# open-usb-can.net
KiCad netlist of a schematic drawn in EAGLE
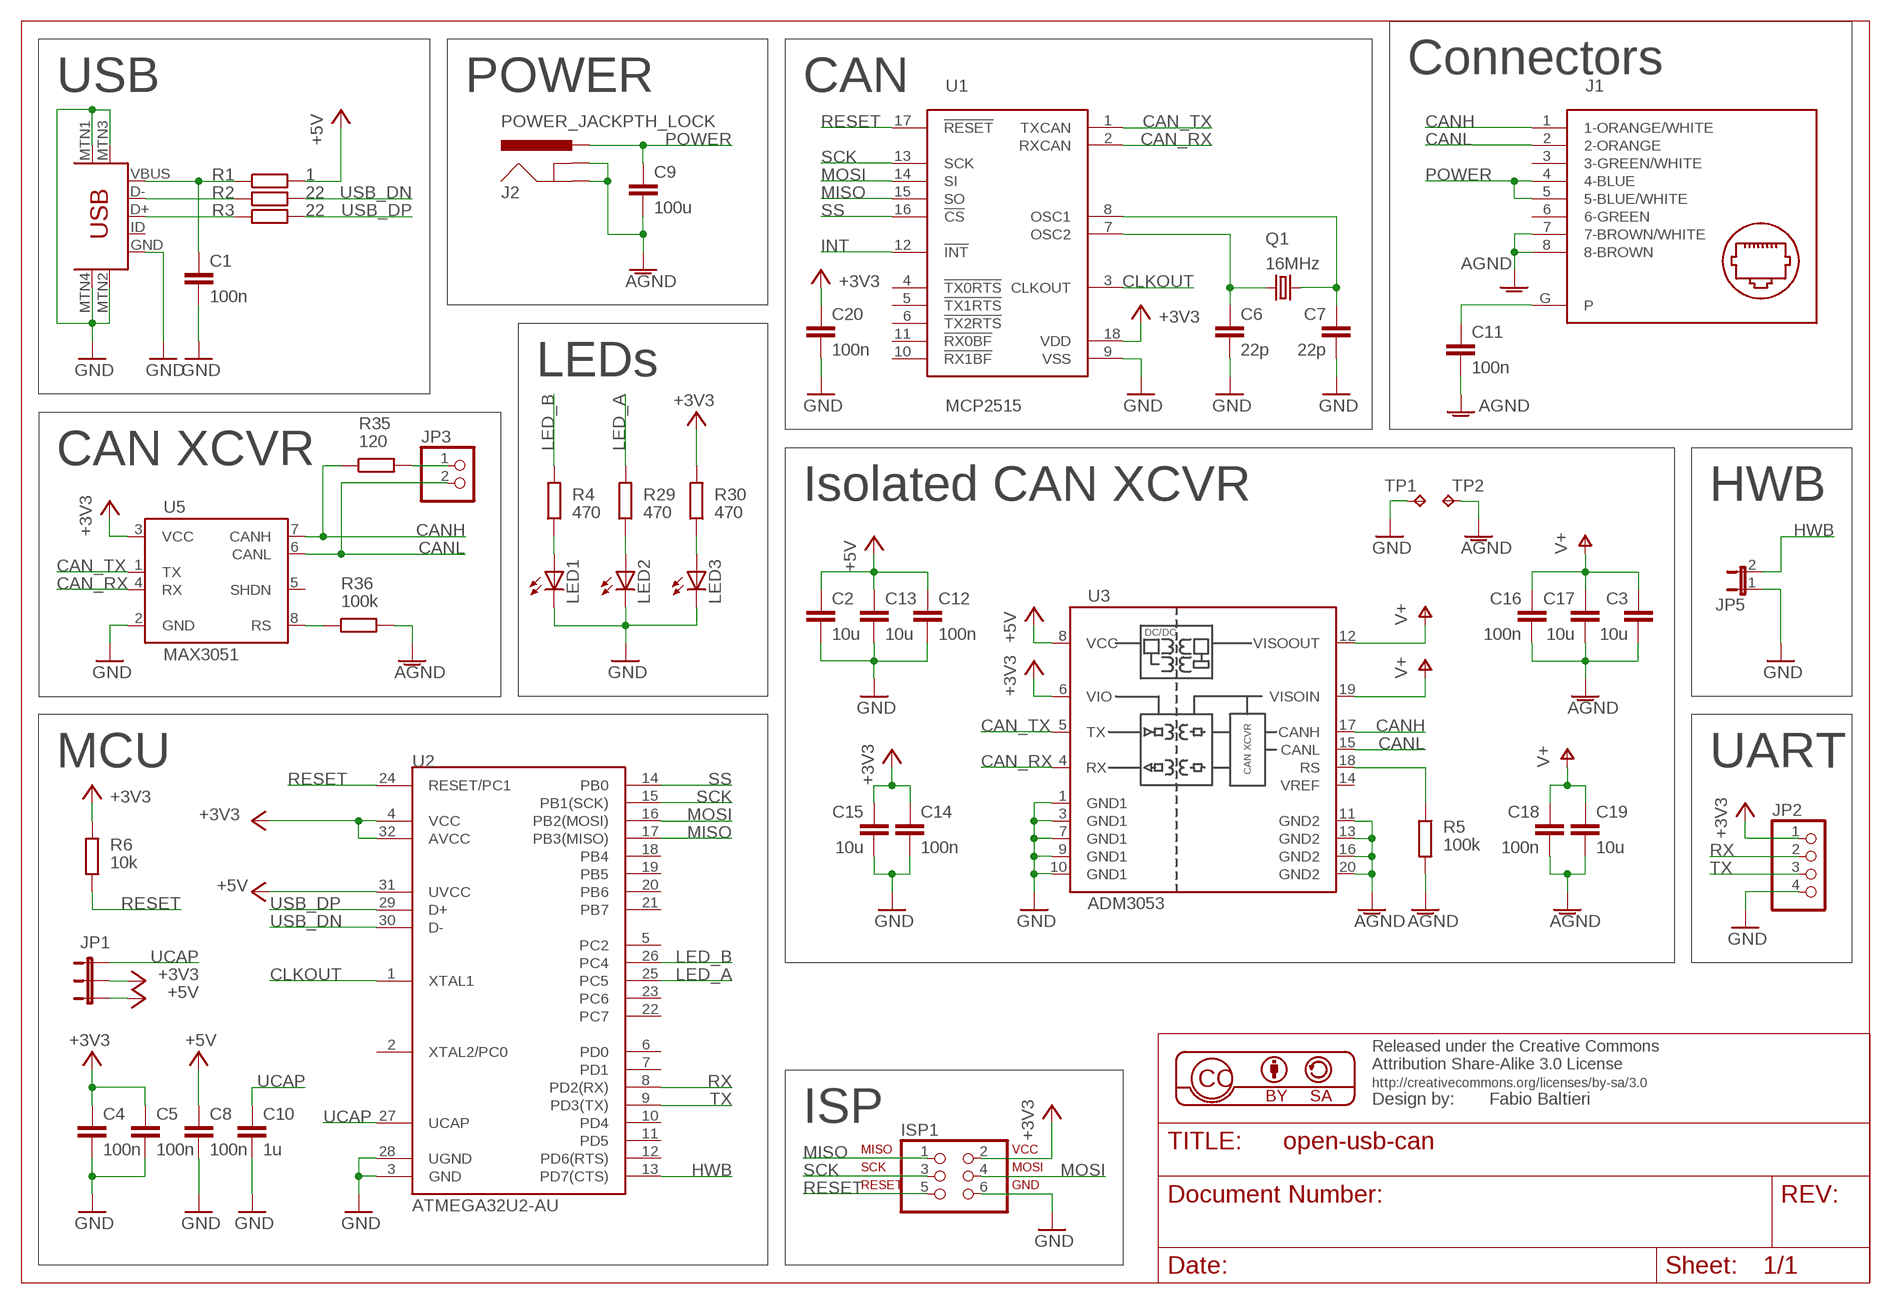
[diagram p0: schematic, sheet 1]

(export (version "E")
  (design (tool "Eeschema 10.0.6"))
  (components
    (comp (ref "C1")
      (value "100n")
      (footprint "eagle-import:C0805")
      (libsource (lib "eagle-import") (part "C-EUC0805"))
    )
    (comp (ref "C2")
      (value "10u")
      (footprint "eagle-import:C0805")
      (libsource (lib "eagle-import") (part "C-EUC0805"))
    )
    (comp (ref "C3")
      (value "10u")
      (footprint "eagle-import:C0805")
      (libsource (lib "eagle-import") (part "C-EUC0805"))
    )
    (comp (ref "C4")
      (value "100n")
      (footprint "eagle-import:C0805")
      (libsource (lib "eagle-import") (part "C-EUC0805"))
    )
    (comp (ref "C5")
      (value "100n")
      (footprint "eagle-import:C0805")
      (libsource (lib "eagle-import") (part "C-EUC0805"))
    )
    (comp (ref "C6")
      (value "22p")
      (footprint "eagle-import:C0805")
      (libsource (lib "eagle-import") (part "C-EUC0805"))
    )
    (comp (ref "C7")
      (value "22p")
      (footprint "eagle-import:C0805")
      (libsource (lib "eagle-import") (part "C-EUC0805"))
    )
    (comp (ref "C8")
      (value "100n")
      (footprint "eagle-import:C0805")
      (libsource (lib "eagle-import") (part "C-EUC0805"))
    )
    (comp (ref "C9")
      (value "100u")
      (footprint "eagle-import:C0805")
      (libsource (lib "eagle-import") (part "C-EUC0805"))
    )
    (comp (ref "C10")
      (value "1u")
      (footprint "eagle-import:C0805")
      (libsource (lib "eagle-import") (part "C-EUC0805"))
    )
    (comp (ref "C11")
      (value "100n")
      (footprint "eagle-import:C0805")
      (libsource (lib "eagle-import") (part "C-EUC0805"))
    )
    (comp (ref "C12")
      (value "100n")
      (footprint "eagle-import:C0805")
      (libsource (lib "eagle-import") (part "C-EUC0805"))
    )
    (comp (ref "C13")
      (value "10u")
      (footprint "eagle-import:C0805")
      (libsource (lib "eagle-import") (part "C-EUC0805"))
    )
    (comp (ref "C14")
      (value "100n")
      (footprint "eagle-import:C0805")
      (libsource (lib "eagle-import") (part "C-EUC0805"))
    )
    (comp (ref "C15")
      (value "10u")
      (footprint "eagle-import:C0805")
      (libsource (lib "eagle-import") (part "C-EUC0805"))
    )
    (comp (ref "C16")
      (value "100n")
      (footprint "eagle-import:C0805")
      (libsource (lib "eagle-import") (part "C-EUC0805"))
    )
    (comp (ref "C17")
      (value "10u")
      (footprint "eagle-import:C0805")
      (libsource (lib "eagle-import") (part "C-EUC0805"))
    )
    (comp (ref "C18")
      (value "100n")
      (footprint "eagle-import:C0805")
      (libsource (lib "eagle-import") (part "C-EUC0805"))
    )
    (comp (ref "C19")
      (value "10u")
      (footprint "eagle-import:C0805")
      (libsource (lib "eagle-import") (part "C-EUC0805"))
    )
    (comp (ref "C20")
      (value "100n")
      (footprint "eagle-import:C0805")
      (libsource (lib "eagle-import") (part "C-EUC0805"))
    )
    (comp (ref "ISP1")
      (value "ISP-AVR910PTH")
      (footprint "eagle-import:2X03")
      (libsource (lib "eagle-import") (part "ISP-AVR910PTH"))
    )
    (comp (ref "J1")
      (value "NE8FAH")
      (footprint "eagle-import:NE8FAH")
      (libsource (lib "eagle-import") (part "NE8FAH"))
    )
    (comp (ref "J2")
      (value "POWER_JACKPTH_LOCK")
      (footprint "eagle-import:POWER_JACK_PTH_LOCK")
      (libsource (lib "eagle-import") (part "POWER_JACKPTH_LOCK"))
    )
    (comp (ref "JP1")
      (value "JUMPER-3SMD")
      (footprint "eagle-import:SJ_3")
      (libsource (lib "eagle-import") (part "JUMPER-3SMD"))
    )
    (comp (ref "JP2")
      (value "PINHD-1X4")
      (footprint "eagle-import:1X04")
      (libsource (lib "eagle-import") (part "PINHD-1X4"))
    )
    (comp (ref "JP3")
      (value "PINHD-1X2")
      (footprint "eagle-import:1X02")
      (libsource (lib "eagle-import") (part "PINHD-1X2"))
    )
    (comp (ref "JP5")
      (value "JUMPER-2-OLDPTH")
      (footprint "eagle-import:1X02")
      (libsource (lib "eagle-import") (part "JUMPER-2-OLDPTH"))
    )
    (comp (ref "LED1")
      (value "LEDCHIPLED_1206")
      (footprint "eagle-import:CHIPLED_1206")
      (libsource (lib "eagle-import") (part "LEDCHIPLED_1206"))
    )
    (comp (ref "LED2")
      (value "LEDCHIPLED_1206")
      (footprint "eagle-import:CHIPLED_1206")
      (libsource (lib "eagle-import") (part "LEDCHIPLED_1206"))
    )
    (comp (ref "LED3")
      (value "LEDCHIPLED_1206")
      (footprint "eagle-import:CHIPLED_1206")
      (libsource (lib "eagle-import") (part "LEDCHIPLED_1206"))
    )
    (comp (ref "Q1")
      (value "16MHz")
      (footprint "eagle-import:HC49U-V")
      (libsource (lib "eagle-import") (part "CRYSTALHC49UV"))
    )
    (comp (ref "R1")
      (value "1")
      (footprint "eagle-import:R0603")
      (libsource (lib "eagle-import") (part "R-EU_R0603"))
    )
    (comp (ref "R2")
      (value "22")
      (footprint "eagle-import:R0603")
      (libsource (lib "eagle-import") (part "R-EU_R0603"))
    )
    (comp (ref "R3")
      (value "22")
      (footprint "eagle-import:R0603")
      (libsource (lib "eagle-import") (part "R-EU_R0603"))
    )
    (comp (ref "R4")
      (value "470")
      (footprint "eagle-import:R0603")
      (libsource (lib "eagle-import") (part "R-EU_R0603"))
    )
    (comp (ref "R5")
      (value "100k")
      (footprint "eagle-import:R0603")
      (libsource (lib "eagle-import") (part "R-EU_R0603"))
    )
    (comp (ref "R6")
      (value "10k")
      (footprint "eagle-import:R0603")
      (libsource (lib "eagle-import") (part "R-EU_R0603"))
    )
    (comp (ref "R29")
      (value "470")
      (footprint "eagle-import:R0603")
      (libsource (lib "eagle-import") (part "R-EU_R0603"))
    )
    (comp (ref "R30")
      (value "470")
      (footprint "eagle-import:R0603")
      (libsource (lib "eagle-import") (part "R-EU_R0603"))
    )
    (comp (ref "R35")
      (value "120")
      (footprint "eagle-import:R0603")
      (libsource (lib "eagle-import") (part "R-EU_R0603"))
    )
    (comp (ref "R36")
      (value "100k")
      (footprint "eagle-import:R0603")
      (libsource (lib "eagle-import") (part "R-EU_R0603"))
    )
    (comp (ref "TP1")
      (value "TPTP16SQ")
      (footprint "eagle-import:TP16SQ")
      (libsource (lib "eagle-import") (part "TPTP16SQ"))
    )
    (comp (ref "TP2")
      (value "TPTP16SQ")
      (footprint "eagle-import:TP16SQ")
      (libsource (lib "eagle-import") (part "TPTP16SQ"))
    )
    (comp (ref "U$2")
      (value "USB-MINIB-5PIN")
      (footprint "eagle-import:USB-MINIB")
      (libsource (lib "eagle-import") (part "USB-MINIB-5PIN"))
    )
    (comp (ref "U1")
      (value "MCP2515")
      (footprint "eagle-import:SO-18DW")
      (libsource (lib "eagle-import") (part "MCP2515"))
    )
    (comp (ref "U2")
      (value "ATMEGA32U2-AU")
      (footprint "eagle-import:TQFP32-08")
      (libsource (lib "eagle-import") (part "ATMEGA8U2AU"))
    )
    (comp (ref "U3")
      (value "ADM3053")
      (footprint "eagle-import:SO20W")
      (libsource (lib "eagle-import") (part "ADM3053"))
    )
    (comp (ref "U5")
      (value "MAX3051")
      (footprint "eagle-import:SO08")
      (libsource (lib "eagle-import") (part "MAX3051"))
    )
  )
  (nets
    (net (code "1") (name "+3V3") (class "Default")
      (node (ref "C14") (pin "1") (pinfunction "1_1") (pintype "passive"))
      (node (ref "C15") (pin "1") (pinfunction "1_1") (pintype "passive"))
      (node (ref "C20") (pin "1") (pinfunction "1_1") (pintype "passive"))
      (node (ref "C4") (pin "1") (pinfunction "1_1") (pintype "passive"))
      (node (ref "C5") (pin "1") (pinfunction "1_1") (pintype "passive"))
      (node (ref "ISP1") (pin "2") (pinfunction "2_2") (pintype "passive"))
      (node (ref "JP1") (pin "2") (pinfunction "2_2") (pintype "passive"))
      (node (ref "JP2") (pin "1") (pinfunction "1_1") (pintype "passive"))
      (node (ref "R30") (pin "2") (pinfunction "2_2") (pintype "passive"))
      (node (ref "R6") (pin "1") (pinfunction "1_1") (pintype "passive"))
      (node (ref "U1") (pin "18") (pinfunction "VDD_18") (pintype "power_in"))
      (node (ref "U2") (pin "32") (pinfunction "AVCC_32") (pintype "bidirectional"))
      (node (ref "U2") (pin "4") (pinfunction "VCC_4") (pintype "bidirectional"))
      (node (ref "U3") (pin "6") (pinfunction "VIO_6") (pintype "bidirectional"))
      (node (ref "U5") (pin "3") (pinfunction "VCC_3") (pintype "bidirectional"))
    )
    (net (code "2") (name "+5V") (class "Default")
      (node (ref "C12") (pin "1") (pinfunction "1_1") (pintype "passive"))
      (node (ref "C13") (pin "1") (pinfunction "1_1") (pintype "passive"))
      (node (ref "C2") (pin "1") (pinfunction "1_1") (pintype "passive"))
      (node (ref "C8") (pin "1") (pinfunction "1_1") (pintype "passive"))
      (node (ref "JP1") (pin "1") (pinfunction "1_1") (pintype "passive"))
      (node (ref "R1") (pin "2") (pinfunction "2_2") (pintype "passive"))
      (node (ref "U2") (pin "31") (pinfunction "UVCC_31") (pintype "bidirectional"))
      (node (ref "U3") (pin "8") (pinfunction "VCC_8") (pintype "bidirectional"))
    )
    (net (code "3") (name "/CANH") (class "Default")
      (node (ref "J1") (pin "1") (pinfunction "1-ORANGE/WHITE_1") (pintype "bidirectional"))
      (node (ref "R35") (pin "1") (pinfunction "1_1") (pintype "passive"))
      (node (ref "U3") (pin "17") (pinfunction "CANH_17") (pintype "bidirectional"))
      (node (ref "U5") (pin "7") (pinfunction "CANH_7") (pintype "bidirectional"))
    )
    (net (code "4") (name "/CANL") (class "Default")
      (node (ref "J1") (pin "2") (pinfunction "2-ORANGE_2") (pintype "bidirectional"))
      (node (ref "JP3") (pin "2") (pinfunction "2_2") (pintype "passive"))
      (node (ref "U3") (pin "15") (pinfunction "CANL_15") (pintype "bidirectional"))
      (node (ref "U5") (pin "6") (pinfunction "CANL_6") (pintype "bidirectional"))
    )
    (net (code "5") (name "/CAN_RX") (class "Default")
      (node (ref "U1") (pin "2") (pinfunction "RXCAN_2") (pintype "bidirectional"))
      (node (ref "U3") (pin "4") (pinfunction "RX_4") (pintype "bidirectional"))
      (node (ref "U5") (pin "4") (pinfunction "RX_4") (pintype "bidirectional"))
    )
    (net (code "6") (name "/CAN_TX") (class "Default")
      (node (ref "U1") (pin "1") (pinfunction "TXCAN_1") (pintype "bidirectional"))
      (node (ref "U3") (pin "5") (pinfunction "TX_5") (pintype "bidirectional"))
      (node (ref "U5") (pin "1") (pinfunction "TX_1") (pintype "bidirectional"))
    )
    (net (code "7") (name "/CLKOUT") (class "Default")
      (node (ref "U1") (pin "3") (pinfunction "CLKOUT_3") (pintype "bidirectional"))
      (node (ref "U2") (pin "1") (pinfunction "XTAL1_1") (pintype "bidirectional"))
    )
    (net (code "8") (name "/HWB") (class "Default")
      (node (ref "JP5") (pin "2") (pinfunction "2_2") (pintype "passive"))
      (node (ref "U2") (pin "13") (pinfunction "PD7(CTS)_13") (pintype "bidirectional"))
    )
    (net (code "9") (name "/INT") (class "Default")
      (node (ref "U1") (pin "12") (pinfunction "~{INT}_12") (pintype "bidirectional"))
    )
    (net (code "10") (name "/LED_A") (class "Default")
      (node (ref "R29") (pin "2") (pinfunction "2_2") (pintype "passive"))
      (node (ref "U2") (pin "25") (pinfunction "PC5_25") (pintype "bidirectional"))
    )
    (net (code "11") (name "/LED_B") (class "Default")
      (node (ref "R4") (pin "2") (pinfunction "2_2") (pintype "passive"))
      (node (ref "U2") (pin "26") (pinfunction "PC4_26") (pintype "bidirectional"))
    )
    (net (code "12") (name "/MISO") (class "Default")
      (node (ref "ISP1") (pin "1") (pinfunction "1_1") (pintype "passive"))
      (node (ref "U1") (pin "15") (pinfunction "SO_15") (pintype "bidirectional"))
      (node (ref "U2") (pin "17") (pinfunction "PB3(MISO)_17") (pintype "bidirectional"))
    )
    (net (code "13") (name "/MOSI") (class "Default")
      (node (ref "ISP1") (pin "4") (pinfunction "4_4") (pintype "passive"))
      (node (ref "U1") (pin "14") (pinfunction "SI_14") (pintype "bidirectional"))
      (node (ref "U2") (pin "16") (pinfunction "PB2(MOSI)_16") (pintype "bidirectional"))
    )
    (net (code "14") (name "/POWER") (class "Default")
      (node (ref "C9") (pin "1") (pinfunction "1_1") (pintype "passive"))
      (node (ref "J1") (pin "4") (pinfunction "4-BLUE_4") (pintype "bidirectional"))
      (node (ref "J1") (pin "5") (pinfunction "5-BLUE/WHITE_5") (pintype "bidirectional"))
      (node (ref "J2") (pin "PWR") (pinfunction "PWR_PWR") (pintype "bidirectional"))
    )
    (net (code "15") (name "/RESET") (class "Default")
      (node (ref "ISP1") (pin "5") (pinfunction "5_5") (pintype "passive"))
      (node (ref "R6") (pin "2") (pinfunction "2_2") (pintype "passive"))
      (node (ref "U1") (pin "17") (pinfunction "~{RESET}_17") (pintype "bidirectional"))
      (node (ref "U2") (pin "24") (pinfunction "RESET/PC1_24") (pintype "bidirectional"))
    )
    (net (code "16") (name "/RX") (class "Default")
      (node (ref "JP2") (pin "2") (pinfunction "2_2") (pintype "passive"))
      (node (ref "U2") (pin "8") (pinfunction "PD2(RX)_8") (pintype "bidirectional"))
    )
    (net (code "17") (name "/SCK") (class "Default")
      (node (ref "ISP1") (pin "3") (pinfunction "3_3") (pintype "passive"))
      (node (ref "U1") (pin "13") (pinfunction "SCK_13") (pintype "bidirectional"))
      (node (ref "U2") (pin "15") (pinfunction "PB1(SCK)_15") (pintype "bidirectional"))
    )
    (net (code "18") (name "/SS") (class "Default")
      (node (ref "U1") (pin "16") (pinfunction "~{CS}_16") (pintype "bidirectional"))
      (node (ref "U2") (pin "14") (pinfunction "PB0_14") (pintype "bidirectional"))
    )
    (net (code "19") (name "/TX") (class "Default")
      (node (ref "JP2") (pin "3") (pinfunction "3_3") (pintype "passive"))
      (node (ref "U2") (pin "9") (pinfunction "PD3(TX)_9") (pintype "bidirectional"))
    )
    (net (code "20") (name "/UCAP") (class "Default")
      (node (ref "C10") (pin "1") (pinfunction "1_1") (pintype "passive"))
      (node (ref "JP1") (pin "3") (pinfunction "3_3") (pintype "passive"))
      (node (ref "U2") (pin "27") (pinfunction "UCAP_27") (pintype "bidirectional"))
    )
    (net (code "21") (name "/USB_DN") (class "Default")
      (node (ref "R2") (pin "2") (pinfunction "2_2") (pintype "passive"))
      (node (ref "U2") (pin "30") (pinfunction "D-_30") (pintype "bidirectional"))
    )
    (net (code "22") (name "/USB_DP") (class "Default")
      (node (ref "R3") (pin "2") (pinfunction "2_2") (pintype "passive"))
      (node (ref "U2") (pin "29") (pinfunction "D+_29") (pintype "bidirectional"))
    )
    (net (code "23") (name "AGND") (class "Default")
      (node (ref "C11") (pin "2") (pinfunction "2_2") (pintype "passive"))
      (node (ref "C16") (pin "2") (pinfunction "2_2") (pintype "passive"))
      (node (ref "C17") (pin "2") (pinfunction "2_2") (pintype "passive"))
      (node (ref "C18") (pin "2") (pinfunction "2_2") (pintype "passive"))
      (node (ref "C19") (pin "2") (pinfunction "2_2") (pintype "passive"))
      (node (ref "C3") (pin "2") (pinfunction "2_2") (pintype "passive"))
      (node (ref "C9") (pin "2") (pinfunction "2_2") (pintype "passive"))
      (node (ref "J1") (pin "7") (pinfunction "7-BROWN/WHITE_7") (pintype "bidirectional"))
      (node (ref "J1") (pin "8") (pinfunction "8-BROWN_8") (pintype "bidirectional"))
      (node (ref "J2") (pin "GND") (pinfunction "GND_GND") (pintype "bidirectional"))
      (node (ref "J2") (pin "GNDBREAK") (pinfunction "GNDBREAK_GNDBREAK") (pintype "bidirectional"))
      (node (ref "R36") (pin "2") (pinfunction "2_2") (pintype "passive"))
      (node (ref "R5") (pin "2") (pinfunction "2_2") (pintype "passive"))
      (node (ref "TP2") (pin "TP") (pinfunction "TP_TP") (pintype "input"))
      (node (ref "U3") (pin "11") (pinfunction "GND2_11") (pintype "bidirectional"))
      (node (ref "U3") (pin "13") (pinfunction "GND2_13") (pintype "bidirectional"))
      (node (ref "U3") (pin "16") (pinfunction "GND2_16") (pintype "bidirectional"))
      (node (ref "U3") (pin "20") (pinfunction "GND2_20") (pintype "bidirectional"))
    )
    (net (code "24") (name "GND") (class "Default")
      (node (ref "C1") (pin "2") (pinfunction "2_2") (pintype "passive"))
      (node (ref "C10") (pin "2") (pinfunction "2_2") (pintype "passive"))
      (node (ref "C12") (pin "2") (pinfunction "2_2") (pintype "passive"))
      (node (ref "C13") (pin "2") (pinfunction "2_2") (pintype "passive"))
      (node (ref "C14") (pin "2") (pinfunction "2_2") (pintype "passive"))
      (node (ref "C15") (pin "2") (pinfunction "2_2") (pintype "passive"))
      (node (ref "C2") (pin "2") (pinfunction "2_2") (pintype "passive"))
      (node (ref "C20") (pin "2") (pinfunction "2_2") (pintype "passive"))
      (node (ref "C4") (pin "2") (pinfunction "2_2") (pintype "passive"))
      (node (ref "C5") (pin "2") (pinfunction "2_2") (pintype "passive"))
      (node (ref "C6") (pin "2") (pinfunction "2_2") (pintype "passive"))
      (node (ref "C7") (pin "2") (pinfunction "2_2") (pintype "passive"))
      (node (ref "C8") (pin "2") (pinfunction "2_2") (pintype "passive"))
      (node (ref "ISP1") (pin "6") (pinfunction "6_6") (pintype "passive"))
      (node (ref "JP2") (pin "4") (pinfunction "4_4") (pintype "passive"))
      (node (ref "JP5") (pin "1") (pinfunction "1_1") (pintype "passive"))
      (node (ref "LED1") (pin "C") (pinfunction "C_C") (pintype "passive"))
      (node (ref "LED2") (pin "C") (pinfunction "C_C") (pintype "passive"))
      (node (ref "LED3") (pin "C") (pinfunction "C_C") (pintype "passive"))
      (node (ref "TP1") (pin "TP") (pinfunction "TP_TP") (pintype "input"))
      (node (ref "U$2") (pin "GND") (pinfunction "GND_GND") (pintype "bidirectional"))
      (node (ref "U$2") (pin "MTN1") (pinfunction "MTN2_MTN1") (pintype "bidirectional"))
      (node (ref "U$2") (pin "MTN2") (pinfunction "MTN3_MTN2") (pintype "bidirectional"))
      (node (ref "U$2") (pin "MTN3") (pinfunction "MTN1_MTN3") (pintype "bidirectional"))
      (node (ref "U$2") (pin "MTN4") (pinfunction "MTN4_MTN4") (pintype "bidirectional"))
      (node (ref "U1") (pin "9") (pinfunction "VSS_9") (pintype "power_in"))
      (node (ref "U2") (pin "28") (pinfunction "UGND_28") (pintype "bidirectional"))
      (node (ref "U2") (pin "3") (pinfunction "GND_3") (pintype "bidirectional"))
      (node (ref "U3") (pin "1") (pinfunction "GND1_1") (pintype "bidirectional"))
      (node (ref "U3") (pin "10") (pinfunction "GND1_10") (pintype "bidirectional"))
      (node (ref "U3") (pin "3") (pinfunction "GND1_3") (pintype "bidirectional"))
      (node (ref "U3") (pin "7") (pinfunction "GND1_7") (pintype "bidirectional"))
      (node (ref "U3") (pin "9") (pinfunction "GND1_9") (pintype "bidirectional"))
      (node (ref "U5") (pin "2") (pinfunction "GND_2") (pintype "bidirectional"))
    )
    (net (code "25") (name "Net-(C1-Pad1)") (class "Default")
      (node (ref "C1") (pin "1") (pinfunction "1_1") (pintype "passive"))
      (node (ref "R1") (pin "1") (pinfunction "1_1") (pintype "passive"))
      (node (ref "U$2") (pin "VBUS") (pinfunction "VBUS_VBUS") (pintype "bidirectional"))
    )
    (net (code "26") (name "Net-(J1-P)") (class "Default")
      (node (ref "C11") (pin "1") (pinfunction "1_1") (pintype "passive"))
      (node (ref "J1") (pin "G") (pinfunction "P_G") (pintype "bidirectional"))
    )
    (net (code "27") (name "Net-(JP3-Pad1)") (class "Default")
      (node (ref "JP3") (pin "1") (pinfunction "1_1") (pintype "passive"))
      (node (ref "R35") (pin "2") (pinfunction "2_2") (pintype "passive"))
    )
    (net (code "28") (name "Net-(LED1-PadA)") (class "Default")
      (node (ref "LED1") (pin "A") (pinfunction "A_A") (pintype "passive"))
      (node (ref "R4") (pin "1") (pinfunction "1_1") (pintype "passive"))
    )
    (net (code "29") (name "Net-(LED2-PadA)") (class "Default")
      (node (ref "LED2") (pin "A") (pinfunction "A_A") (pintype "passive"))
      (node (ref "R29") (pin "1") (pinfunction "1_1") (pintype "passive"))
    )
    (net (code "30") (name "Net-(LED3-PadA)") (class "Default")
      (node (ref "LED3") (pin "A") (pinfunction "A_A") (pintype "passive"))
      (node (ref "R30") (pin "1") (pinfunction "1_1") (pintype "passive"))
    )
    (net (code "31") (name "Net-(R2-Pad1)") (class "Default")
      (node (ref "R2") (pin "1") (pinfunction "1_1") (pintype "passive"))
      (node (ref "U$2") (pin "D-") (pinfunction "D-_D-") (pintype "bidirectional"))
    )
    (net (code "32") (name "Net-(R3-Pad1)") (class "Default")
      (node (ref "R3") (pin "1") (pinfunction "1_1") (pintype "passive"))
      (node (ref "U$2") (pin "D+") (pinfunction "D+_D+") (pintype "bidirectional"))
    )
    (net (code "33") (name "Net-(U1-OSC1)") (class "Default")
      (node (ref "C7") (pin "1") (pinfunction "1_1") (pintype "passive"))
      (node (ref "Q1") (pin "2") (pinfunction "2_2") (pintype "passive"))
      (node (ref "U1") (pin "8") (pinfunction "OSC1_8") (pintype "bidirectional"))
    )
    (net (code "34") (name "Net-(U1-OSC2)") (class "Default")
      (node (ref "C6") (pin "1") (pinfunction "1_1") (pintype "passive"))
      (node (ref "Q1") (pin "1") (pinfunction "1_1") (pintype "passive"))
      (node (ref "U1") (pin "7") (pinfunction "OSC2_7") (pintype "bidirectional"))
    )
    (net (code "35") (name "Net-(U3-RS)") (class "Default")
      (node (ref "R5") (pin "1") (pinfunction "1_1") (pintype "passive"))
      (node (ref "U3") (pin "18") (pinfunction "RS_18") (pintype "bidirectional"))
    )
    (net (code "36") (name "Net-(U5-RS)") (class "Default")
      (node (ref "R36") (pin "1") (pinfunction "1_1") (pintype "passive"))
      (node (ref "U5") (pin "8") (pinfunction "RS_8") (pintype "bidirectional"))
    )
    (net (code "37") (name "V+") (class "Default")
      (node (ref "C16") (pin "1") (pinfunction "1_1") (pintype "passive"))
      (node (ref "C17") (pin "1") (pinfunction "1_1") (pintype "passive"))
      (node (ref "C18") (pin "1") (pinfunction "1_1") (pintype "passive"))
      (node (ref "C19") (pin "1") (pinfunction "1_1") (pintype "passive"))
      (node (ref "C3") (pin "1") (pinfunction "1_1") (pintype "passive"))
      (node (ref "U3") (pin "12") (pinfunction "VISOOUT_12") (pintype "bidirectional"))
      (node (ref "U3") (pin "19") (pinfunction "VISOIN_19") (pintype "bidirectional"))
    )
    (net (code "38") (name "unconnected-(J1-3-GREEN{slash}WHITE-Pad3)") (class "Default")
      (node (ref "J1") (pin "3") (pinfunction "3-GREEN/WHITE_3") (pintype "bidirectional"))
    )
    (net (code "39") (name "unconnected-(J1-6-GREEN-Pad6)") (class "Default")
      (node (ref "J1") (pin "6") (pinfunction "6-GREEN_6") (pintype "bidirectional"))
    )
    (net (code "40") (name "unconnected-(U$2-PadID)") (class "Default")
      (node (ref "U$2") (pin "ID") (pinfunction "ID_ID") (pintype "bidirectional"))
    )
    (net (code "41") (name "unconnected-(U1-~{RX0BF}-Pad11)") (class "Default")
      (node (ref "U1") (pin "11") (pinfunction "~{RX0BF}_11") (pintype "bidirectional"))
    )
    (net (code "42") (name "unconnected-(U1-~{RX1BF}-Pad10)") (class "Default")
      (node (ref "U1") (pin "10") (pinfunction "~{RX1BF}_10") (pintype "bidirectional"))
    )
    (net (code "43") (name "unconnected-(U1-~{TX0RTS}-Pad4)") (class "Default")
      (node (ref "U1") (pin "4") (pinfunction "~{TX0RTS}_4") (pintype "bidirectional"))
    )
    (net (code "44") (name "unconnected-(U1-~{TX1RTS}-Pad5)") (class "Default")
      (node (ref "U1") (pin "5") (pinfunction "~{TX1RTS}_5") (pintype "bidirectional"))
    )
    (net (code "45") (name "unconnected-(U1-~{TX2RTS}-Pad6)") (class "Default")
      (node (ref "U1") (pin "6") (pinfunction "~{TX2RTS}_6") (pintype "bidirectional"))
    )
    (net (code "46") (name "unconnected-(U2-PB4-Pad18)") (class "Default")
      (node (ref "U2") (pin "18") (pinfunction "PB4_18") (pintype "bidirectional"))
    )
    (net (code "47") (name "unconnected-(U2-PB5-Pad19)") (class "Default")
      (node (ref "U2") (pin "19") (pinfunction "PB5_19") (pintype "bidirectional"))
    )
    (net (code "48") (name "unconnected-(U2-PB6-Pad20)") (class "Default")
      (node (ref "U2") (pin "20") (pinfunction "PB6_20") (pintype "bidirectional"))
    )
    (net (code "49") (name "unconnected-(U2-PB7-Pad21)") (class "Default")
      (node (ref "U2") (pin "21") (pinfunction "PB7_21") (pintype "bidirectional"))
    )
    (net (code "50") (name "unconnected-(U2-PC2-Pad5)") (class "Default")
      (node (ref "U2") (pin "5") (pinfunction "PC2_5") (pintype "bidirectional"))
    )
    (net (code "51") (name "unconnected-(U2-PC6-Pad23)") (class "Default")
      (node (ref "U2") (pin "23") (pinfunction "PC6_23") (pintype "bidirectional"))
    )
    (net (code "52") (name "unconnected-(U2-PC7-Pad22)") (class "Default")
      (node (ref "U2") (pin "22") (pinfunction "PC7_22") (pintype "bidirectional"))
    )
    (net (code "53") (name "unconnected-(U2-PD0-Pad6)") (class "Default")
      (node (ref "U2") (pin "6") (pinfunction "PD0_6") (pintype "bidirectional"))
    )
    (net (code "54") (name "unconnected-(U2-PD1-Pad7)") (class "Default")
      (node (ref "U2") (pin "7") (pinfunction "PD1_7") (pintype "bidirectional"))
    )
    (net (code "55") (name "unconnected-(U2-PD4-Pad10)") (class "Default")
      (node (ref "U2") (pin "10") (pinfunction "PD4_10") (pintype "bidirectional"))
    )
    (net (code "56") (name "unconnected-(U2-PD5-Pad11)") (class "Default")
      (node (ref "U2") (pin "11") (pinfunction "PD5_11") (pintype "bidirectional"))
    )
    (net (code "57") (name "unconnected-(U2-PD6(RTS)-Pad12)") (class "Default")
      (node (ref "U2") (pin "12") (pinfunction "PD6(RTS)_12") (pintype "bidirectional"))
    )
    (net (code "58") (name "unconnected-(U2-XTAL2{slash}PC0-Pad2)") (class "Default")
      (node (ref "U2") (pin "2") (pinfunction "XTAL2/PC0_2") (pintype "bidirectional"))
    )
    (net (code "59") (name "unconnected-(U3-NC-Pad2)") (class "Default")
      (node (ref "U3") (pin "2") (pinfunction "NC_2") (pintype "bidirectional"))
    )
    (net (code "60") (name "unconnected-(U3-VREF-Pad14)") (class "Default")
      (node (ref "U3") (pin "14") (pinfunction "VREF_14") (pintype "bidirectional"))
    )
    (net (code "61") (name "unconnected-(U5-SHDN-Pad5)") (class "Default")
      (node (ref "U5") (pin "5") (pinfunction "SHDN_5") (pintype "bidirectional"))
    )
  )
)
